# BSPD_Schematic_with_latching_fixed_-_2-2.net
KiCad netlist of a schematic drawn in EAGLE
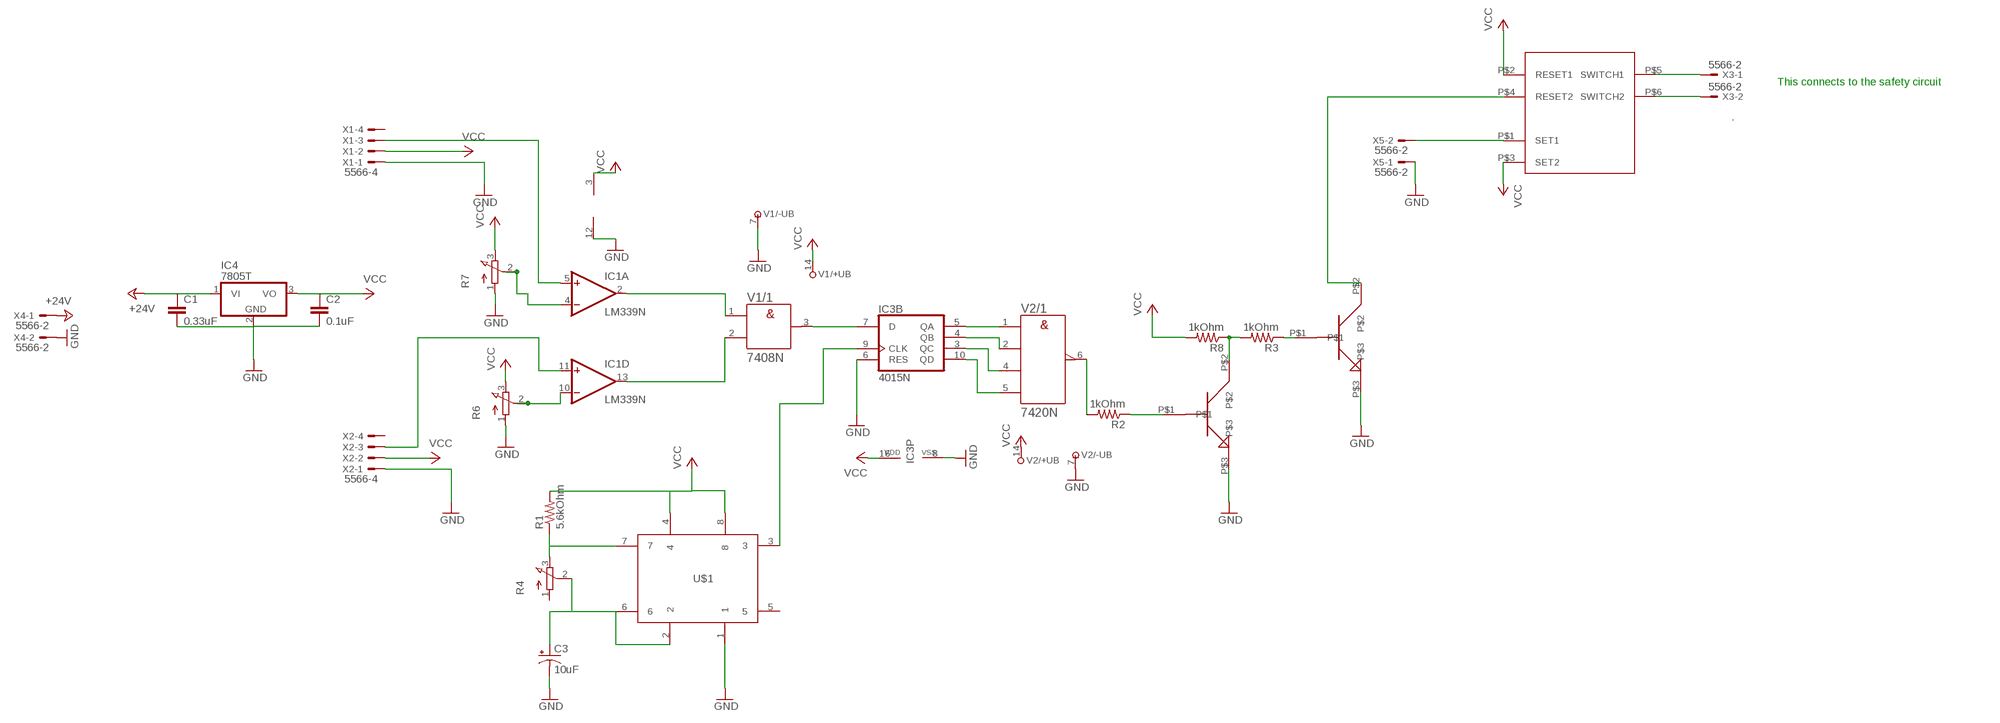
[diagram p0: schematic, sheet 1]

(export (version "E")
  (design (tool "Eeschema 10.0.6"))
  (components
    (comp (ref "C1")
      (value "0.33uF")
      (footprint "eagle-import:CAP-PTH-LARGE")
      (libsource (lib "eagle-import") (part "CAPPTH3"))
    )
    (comp (ref "C2")
      (value "0.1uF")
      (footprint "eagle-import:CAP-PTH-LARGE")
      (libsource (lib "eagle-import") (part "CAPPTH3"))
    )
    (comp (ref "C3")
      (value "10uF")
      (footprint "eagle-import:E2,5-7")
      (libsource (lib "eagle-import") (part "CPOL-USE2.5-7"))
    )
    (comp (ref "IC1")
      (value "LM339N")
      (footprint "eagle-import:DIL14")
      (libsource (lib "eagle-import") (part "LM339N"))
    )
    (comp (ref "IC3")
      (value "4015N")
      (footprint "eagle-import:DIL16")
      (libsource (lib "eagle-import") (part "4015N"))
    )
    (comp (ref "IC4")
      (value "7805T")
      (footprint "eagle-import:TO220H")
      (libsource (lib "eagle-import") (part "78T05"))
    )
    (comp (ref "R1")
      (value "5.6kOhm")
      (footprint "eagle-import:1_6W-RES")
      (libsource (lib "eagle-import") (part "RESISTORPTH-1/6W"))
    )
    (comp (ref "R2")
      (value "1kOhm")
      (footprint "eagle-import:1_6W-RES")
      (libsource (lib "eagle-import") (part "RESISTORPTH-1/6W"))
    )
    (comp (ref "R3")
      (value "1kOhm")
      (footprint "eagle-import:1_6W-RES")
      (libsource (lib "eagle-import") (part "RESISTORPTH-1/6W"))
    )
    (comp (ref "R4")
      (value "3RP/1610N")
      (footprint "eagle-import:3RP_1610N")
      (libsource (lib "eagle-import") (part "3RP/1610N"))
    )
    (comp (ref "R6")
      (value "3RP/1610N")
      (footprint "eagle-import:3RP_1610N")
      (libsource (lib "eagle-import") (part "3RP/1610N"))
    )
    (comp (ref "R7")
      (value "3RP/1610N")
      (footprint "eagle-import:3RP_1610N")
      (libsource (lib "eagle-import") (part "3RP/1610N"))
    )
    (comp (ref "R8")
      (value "1kOhm")
      (footprint "eagle-import:1_6W-RES")
      (libsource (lib "eagle-import") (part "RESISTORPTH-1/6W"))
    )
    (comp (ref "U$1")
      (value "555_TIMER555_TIMER")
      (footprint "eagle-import:DIL08")
      (libsource (lib "eagle-import") (part "555_TIMER555_TIMER"))
    )
    (comp (ref "U$2")
      (value "TRANSISTOR_ZTX653THROUGH_HOLE")
      (footprint "eagle-import:TRANSISTOR")
      (libsource (lib "eagle-import") (part "TRANSISTOR_ZTX653THROUGH_HOLE"))
    )
    (comp (ref "U$3")
      (value "LATCHING_RELAY_G6CK-1117P-US-DC5")
      (footprint "eagle-import:LATCHING_RELAY_G6CK-1117P-US-DC5")
      (libsource (lib "eagle-import") (part "LATCHING_RELAY_G6CK-1117P-US-DC5"))
    )
    (comp (ref "U$4")
      (value "TRANSISTOR_ZTX653THROUGH_HOLE")
      (footprint "eagle-import:TRANSISTOR")
      (libsource (lib "eagle-import") (part "TRANSISTOR_ZTX653THROUGH_HOLE"))
    )
    (comp (ref "V1")
      (value "7408N")
      (footprint "eagle-import:DIL14")
      (libsource (lib "eagle-import") (part "7408N"))
    )
    (comp (ref "V2")
      (value "7420N")
      (footprint "eagle-import:DIL14")
      (libsource (lib "eagle-import") (part "7420N"))
    )
    (comp (ref "X1")
      (value "5566-4")
      (footprint "eagle-import:5566-4")
      (libsource (lib "eagle-import") (part "5566-4"))
    )
    (comp (ref "X2")
      (value "5566-4")
      (footprint "eagle-import:5566-4")
      (libsource (lib "eagle-import") (part "5566-4"))
    )
    (comp (ref "X3")
      (value "5566-2")
      (footprint "eagle-import:5566-2")
      (libsource (lib "eagle-import") (part "5566-2"))
    )
    (comp (ref "X4")
      (value "5566-2")
      (footprint "eagle-import:5566-2")
      (libsource (lib "eagle-import") (part "5566-2"))
    )
    (comp (ref "X5")
      (value "5566-2")
      (footprint "eagle-import:5566-2")
      (libsource (lib "eagle-import") (part "5566-2"))
    )
  )
  (nets
    (net (code "1") (name "+24V") (class "Default")
      (node (ref "C1") (pin "1") (pinfunction "1_1") (pintype "passive"))
      (node (ref "IC4") (pin "1") (pinfunction "VI_1") (pintype "input"))
      (node (ref "X4") (pin "1") (pinfunction "S_1") (pintype "passive"))
    )
    (net (code "2") (name "GND") (class "Default")
      (node (ref "C1") (pin "2") (pinfunction "2_2") (pintype "passive"))
      (node (ref "C2") (pin "2") (pinfunction "2_2") (pintype "passive"))
      (node (ref "C3") (pin "-") (pinfunction "-_-") (pintype "passive"))
      (node (ref "IC1") (pin "12") (pinfunction "GND_12") (pintype "power_in"))
      (node (ref "IC3") (pin "6") (pinfunction "RES_6") (pintype "input"))
      (node (ref "IC3") (pin "8") (pinfunction "VSS_8") (pintype "power_in"))
      (node (ref "IC4") (pin "2") (pinfunction "GND_2") (pintype "passive"))
      (node (ref "R6") (pin "1") (pinfunction "A_1") (pintype "passive"))
      (node (ref "R7") (pin "1") (pinfunction "A_1") (pintype "passive"))
      (node (ref "U$1") (pin "1") (pinfunction "1_1") (pintype "bidirectional"))
      (node (ref "U$2") (pin "P$3") (pinfunction "P$3_P$3") (pintype "bidirectional"))
      (node (ref "U$4") (pin "P$3") (pinfunction "P$3_P$3") (pintype "bidirectional"))
      (node (ref "V1") (pin "7") (pinfunction "-UB_7") (pintype "power_in"))
      (node (ref "V2") (pin "7") (pinfunction "-UB_7") (pintype "power_in"))
      (node (ref "X1") (pin "1") (pinfunction "S_1") (pintype "passive"))
      (node (ref "X2") (pin "1") (pinfunction "S_1") (pintype "passive"))
      (node (ref "X4") (pin "2") (pinfunction "S_2") (pintype "passive"))
      (node (ref "X5") (pin "1") (pinfunction "S_1") (pintype "passive"))
    )
    (net (code "3") (name "Net-(IC1A-+IN)") (class "Default")
      (node (ref "IC1") (pin "5") (pinfunction "+IN_5") (pintype "input"))
      (node (ref "X1") (pin "3") (pinfunction "S_3") (pintype "passive"))
    )
    (net (code "4") (name "Net-(IC1A--IN)") (class "Default")
      (node (ref "IC1") (pin "4") (pinfunction "-IN_4") (pintype "input"))
      (node (ref "R7") (pin "2") (pinfunction "S_2") (pintype "passive"))
    )
    (net (code "5") (name "Net-(IC1A-OUT)") (class "Default")
      (node (ref "IC1") (pin "2") (pinfunction "OUT_2") (pintype "open_collector"))
      (node (ref "V1") (pin "1") (pinfunction "A_1") (pintype "input"))
    )
    (net (code "6") (name "Net-(IC1D-+IN)") (class "Default")
      (node (ref "IC1") (pin "11") (pinfunction "+IN_11") (pintype "input"))
      (node (ref "X2") (pin "3") (pinfunction "S_3") (pintype "passive"))
    )
    (net (code "7") (name "Net-(IC1D--IN)") (class "Default")
      (node (ref "IC1") (pin "10") (pinfunction "-IN_10") (pintype "input"))
      (node (ref "R6") (pin "2") (pinfunction "S_2") (pintype "passive"))
    )
    (net (code "8") (name "Net-(IC1D-OUT)") (class "Default")
      (node (ref "IC1") (pin "13") (pinfunction "OUT_13") (pintype "open_collector"))
      (node (ref "V1") (pin "2") (pinfunction "B_2") (pintype "input"))
    )
    (net (code "9") (name "Net-(IC3B-CLK)") (class "Default")
      (node (ref "IC3") (pin "9") (pinfunction "CLK_9") (pintype "input"))
      (node (ref "U$1") (pin "3") (pinfunction "3_3") (pintype "bidirectional"))
    )
    (net (code "10") (name "Net-(IC3B-D)") (class "Default")
      (node (ref "IC3") (pin "7") (pinfunction "D_7") (pintype "input"))
      (node (ref "V1") (pin "3") (pinfunction "Y_3") (pintype "output"))
    )
    (net (code "11") (name "Net-(IC3B-QA)") (class "Default")
      (node (ref "IC3") (pin "5") (pinfunction "QA_5") (pintype "output"))
      (node (ref "V2") (pin "1") (pinfunction "A_1") (pintype "input"))
    )
    (net (code "12") (name "Net-(IC3B-QB)") (class "Default")
      (node (ref "IC3") (pin "4") (pinfunction "QB_4") (pintype "output"))
      (node (ref "V2") (pin "2") (pinfunction "B_2") (pintype "input"))
    )
    (net (code "13") (name "Net-(IC3B-QC)") (class "Default")
      (node (ref "IC3") (pin "3") (pinfunction "QC_3") (pintype "output"))
      (node (ref "V2") (pin "4") (pinfunction "C_4") (pintype "input"))
    )
    (net (code "14") (name "Net-(IC3B-QD)") (class "Default")
      (node (ref "IC3") (pin "10") (pinfunction "QD_10") (pintype "output"))
      (node (ref "V2") (pin "5") (pinfunction "D_5") (pintype "input"))
    )
    (net (code "15") (name "Net-(R2-Pad1)") (class "Default")
      (node (ref "R2") (pin "1") (pinfunction "1_1") (pintype "passive"))
      (node (ref "U$2") (pin "P$1") (pinfunction "P$1_P$1") (pintype "bidirectional"))
    )
    (net (code "16") (name "Net-(R3-Pad1)") (class "Default")
      (node (ref "R3") (pin "1") (pinfunction "1_1") (pintype "passive"))
      (node (ref "U$4") (pin "P$1") (pinfunction "P$1_P$1") (pintype "bidirectional"))
    )
    (net (code "17") (name "Net-(R3-Pad2)") (class "Default")
      (node (ref "R3") (pin "2") (pinfunction "2_2") (pintype "passive"))
      (node (ref "R8") (pin "1") (pinfunction "1_1") (pintype "passive"))
      (node (ref "U$2") (pin "P$2") (pinfunction "P$2_P$2") (pintype "bidirectional"))
    )
    (net (code "18") (name "Net-(R4-E)") (class "Default")
      (node (ref "R1") (pin "1") (pinfunction "1_1") (pintype "passive"))
      (node (ref "R4") (pin "3") (pinfunction "E_3") (pintype "passive"))
      (node (ref "U$1") (pin "7") (pinfunction "7_7") (pintype "bidirectional"))
    )
    (net (code "19") (name "Net-(R4-S)") (class "Default")
      (node (ref "C3") (pin "+") (pinfunction "+_+") (pintype "passive"))
      (node (ref "R4") (pin "2") (pinfunction "S_2") (pintype "passive"))
      (node (ref "U$1") (pin "2") (pinfunction "2_2") (pintype "bidirectional"))
      (node (ref "U$1") (pin "6") (pinfunction "6_6") (pintype "bidirectional"))
    )
    (net (code "20") (name "Net-(U$3-RESET2)") (class "Default")
      (node (ref "U$3") (pin "P$4") (pinfunction "RESET2_P$4") (pintype "bidirectional"))
      (node (ref "U$4") (pin "P$2") (pinfunction "P$2_P$2") (pintype "bidirectional"))
    )
    (net (code "21") (name "Net-(U$3-SET1)") (class "Default")
      (node (ref "U$3") (pin "P$1") (pinfunction "SET1_P$1") (pintype "bidirectional"))
      (node (ref "X5") (pin "2") (pinfunction "S_2") (pintype "passive"))
    )
    (net (code "22") (name "Net-(U$3-SWITCH1)") (class "Default")
      (node (ref "U$3") (pin "P$5") (pinfunction "SWITCH1_P$5") (pintype "bidirectional"))
      (node (ref "X3") (pin "1") (pinfunction "S_1") (pintype "passive"))
    )
    (net (code "23") (name "Net-(U$3-SWITCH2)") (class "Default")
      (node (ref "U$3") (pin "P$6") (pinfunction "SWITCH2_P$6") (pintype "bidirectional"))
      (node (ref "X3") (pin "2") (pinfunction "S_2") (pintype "passive"))
    )
    (net (code "24") (name "Net-(V2C-Y)") (class "Default")
      (node (ref "R2") (pin "2") (pinfunction "2_2") (pintype "passive"))
      (node (ref "V2") (pin "6") (pinfunction "Y_6") (pintype "output"))
    )
    (net (code "25") (name "VCC") (class "Default")
      (node (ref "C2") (pin "1") (pinfunction "1_1") (pintype "passive"))
      (node (ref "IC1") (pin "3") (pinfunction "V+_3") (pintype "power_in"))
      (node (ref "IC3") (pin "16") (pinfunction "VDD_16") (pintype "power_in"))
      (node (ref "IC4") (pin "3") (pinfunction "VO_3") (pintype "passive"))
      (node (ref "R1") (pin "2") (pinfunction "2_2") (pintype "passive"))
      (node (ref "R6") (pin "3") (pinfunction "E_3") (pintype "passive"))
      (node (ref "R7") (pin "3") (pinfunction "E_3") (pintype "passive"))
      (node (ref "R8") (pin "2") (pinfunction "2_2") (pintype "passive"))
      (node (ref "U$1") (pin "4") (pinfunction "4_4") (pintype "bidirectional"))
      (node (ref "U$1") (pin "8") (pinfunction "8_8") (pintype "bidirectional"))
      (node (ref "U$3") (pin "P$2") (pinfunction "RESET1_P$2") (pintype "bidirectional"))
      (node (ref "U$3") (pin "P$3") (pinfunction "SET2_P$3") (pintype "bidirectional"))
      (node (ref "V1") (pin "14") (pinfunction "+UB_14") (pintype "power_in"))
      (node (ref "V2") (pin "14") (pinfunction "+UB_14") (pintype "power_in"))
      (node (ref "X1") (pin "2") (pinfunction "S_2") (pintype "passive"))
      (node (ref "X2") (pin "2") (pinfunction "S_2") (pintype "passive"))
    )
    (net (code "26") (name "unconnected-(R4-A-Pad1)") (class "Default")
      (node (ref "R4") (pin "1") (pinfunction "A_1") (pintype "passive"))
    )
    (net (code "27") (name "unconnected-(U$1-Pad5)") (class "Default")
      (node (ref "U$1") (pin "5") (pinfunction "5_5") (pintype "bidirectional"))
    )
    (net (code "28") (name "unconnected-(X1D-S-Pad4)") (class "Default")
      (node (ref "X1") (pin "4") (pinfunction "S_4") (pintype "passive"))
    )
    (net (code "29") (name "unconnected-(X2D-S-Pad4)") (class "Default")
      (node (ref "X2") (pin "4") (pinfunction "S_4") (pintype "passive"))
    )
  )
)
